# SheetMS5837.net
KiCad netlist of a schematic drawn in Altium Designer
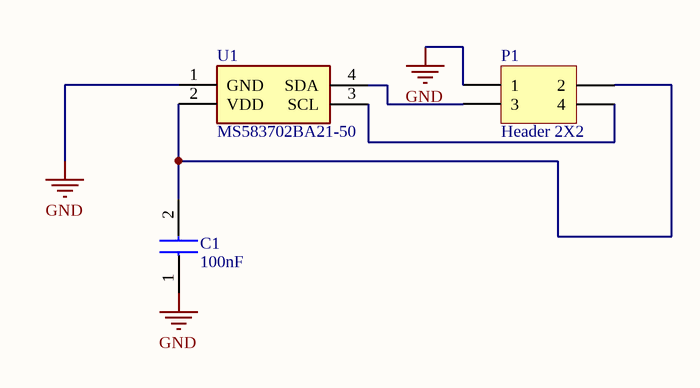
[diagram p0: SheetMS5837.SchDoc]

(export (version "E")
  (design (tool "Eeschema 10.0.6"))
  (components
    (comp (ref "C1")
      (value "100nF")
      (footprint "SamacSys:CAPC2012X94N")
      (description "Capacitor")
      (fields
        (field (name "MANUFACTURER_PART_NUMBER") "08055A130JAT2A")
        (field (name "MOUSER PART NUMBER") "581-08055A130JAT2A")
      )
      (libsource (lib "SamacSys") (part "08055A130JAT2A"))
    )
    (comp (ref "P1")
      (value "Header 2X2")
      (footprint "HDR2X2")
      (description "Header, 2-Pin, Dual row")
      (fields (field (name "PUBLISHER") "Altium Limited"))
      (libsource (lib "Miscellaneous Connectors") (part "Header 2X2"))
    )
    (comp (ref "U1")
      (value "MS583702BA21-50")
      (footprint "SamacSys:MS583702BA0150")
      (description "Undefined or Miscellaneous")
      (fields (field (name "MOUSER PART NUMBER") "824-MS583702BA21-50"))
      (libsource (lib "*") (part "MS583702BA21-50"))
    )
  )
  (nets
    (net (code "1") (name "GND") (class "Default")
      (node (ref "C1") (pin "1") (pinfunction "1_1") (pintype "passive"))
      (node (ref "P1") (pin "1") (pinfunction "1_1") (pintype "passive"))
      (node (ref "U1") (pin "1") (pinfunction "GND_1") (pintype "passive"))
    )
    (net (code "2") (name "Net-(U1-SCL)") (class "Default")
      (node (ref "P1") (pin "4") (pinfunction "4_4") (pintype "passive"))
      (node (ref "U1") (pin "3") (pinfunction "SCL_3") (pintype "passive"))
    )
    (net (code "3") (name "Net-(U1-SDA)") (class "Default")
      (node (ref "P1") (pin "3") (pinfunction "3_3") (pintype "passive"))
      (node (ref "U1") (pin "4") (pinfunction "SDA_4") (pintype "passive"))
    )
    (net (code "4") (name "Net-(U1-VDD)") (class "Default")
      (node (ref "C1") (pin "2") (pinfunction "2_2") (pintype "passive"))
      (node (ref "P1") (pin "2") (pinfunction "2_2") (pintype "passive"))
      (node (ref "U1") (pin "2") (pinfunction "VDD_2") (pintype "passive"))
    )
  )
)
